# design.net
KiCad netlist of a schematic drawn in Altium Designer
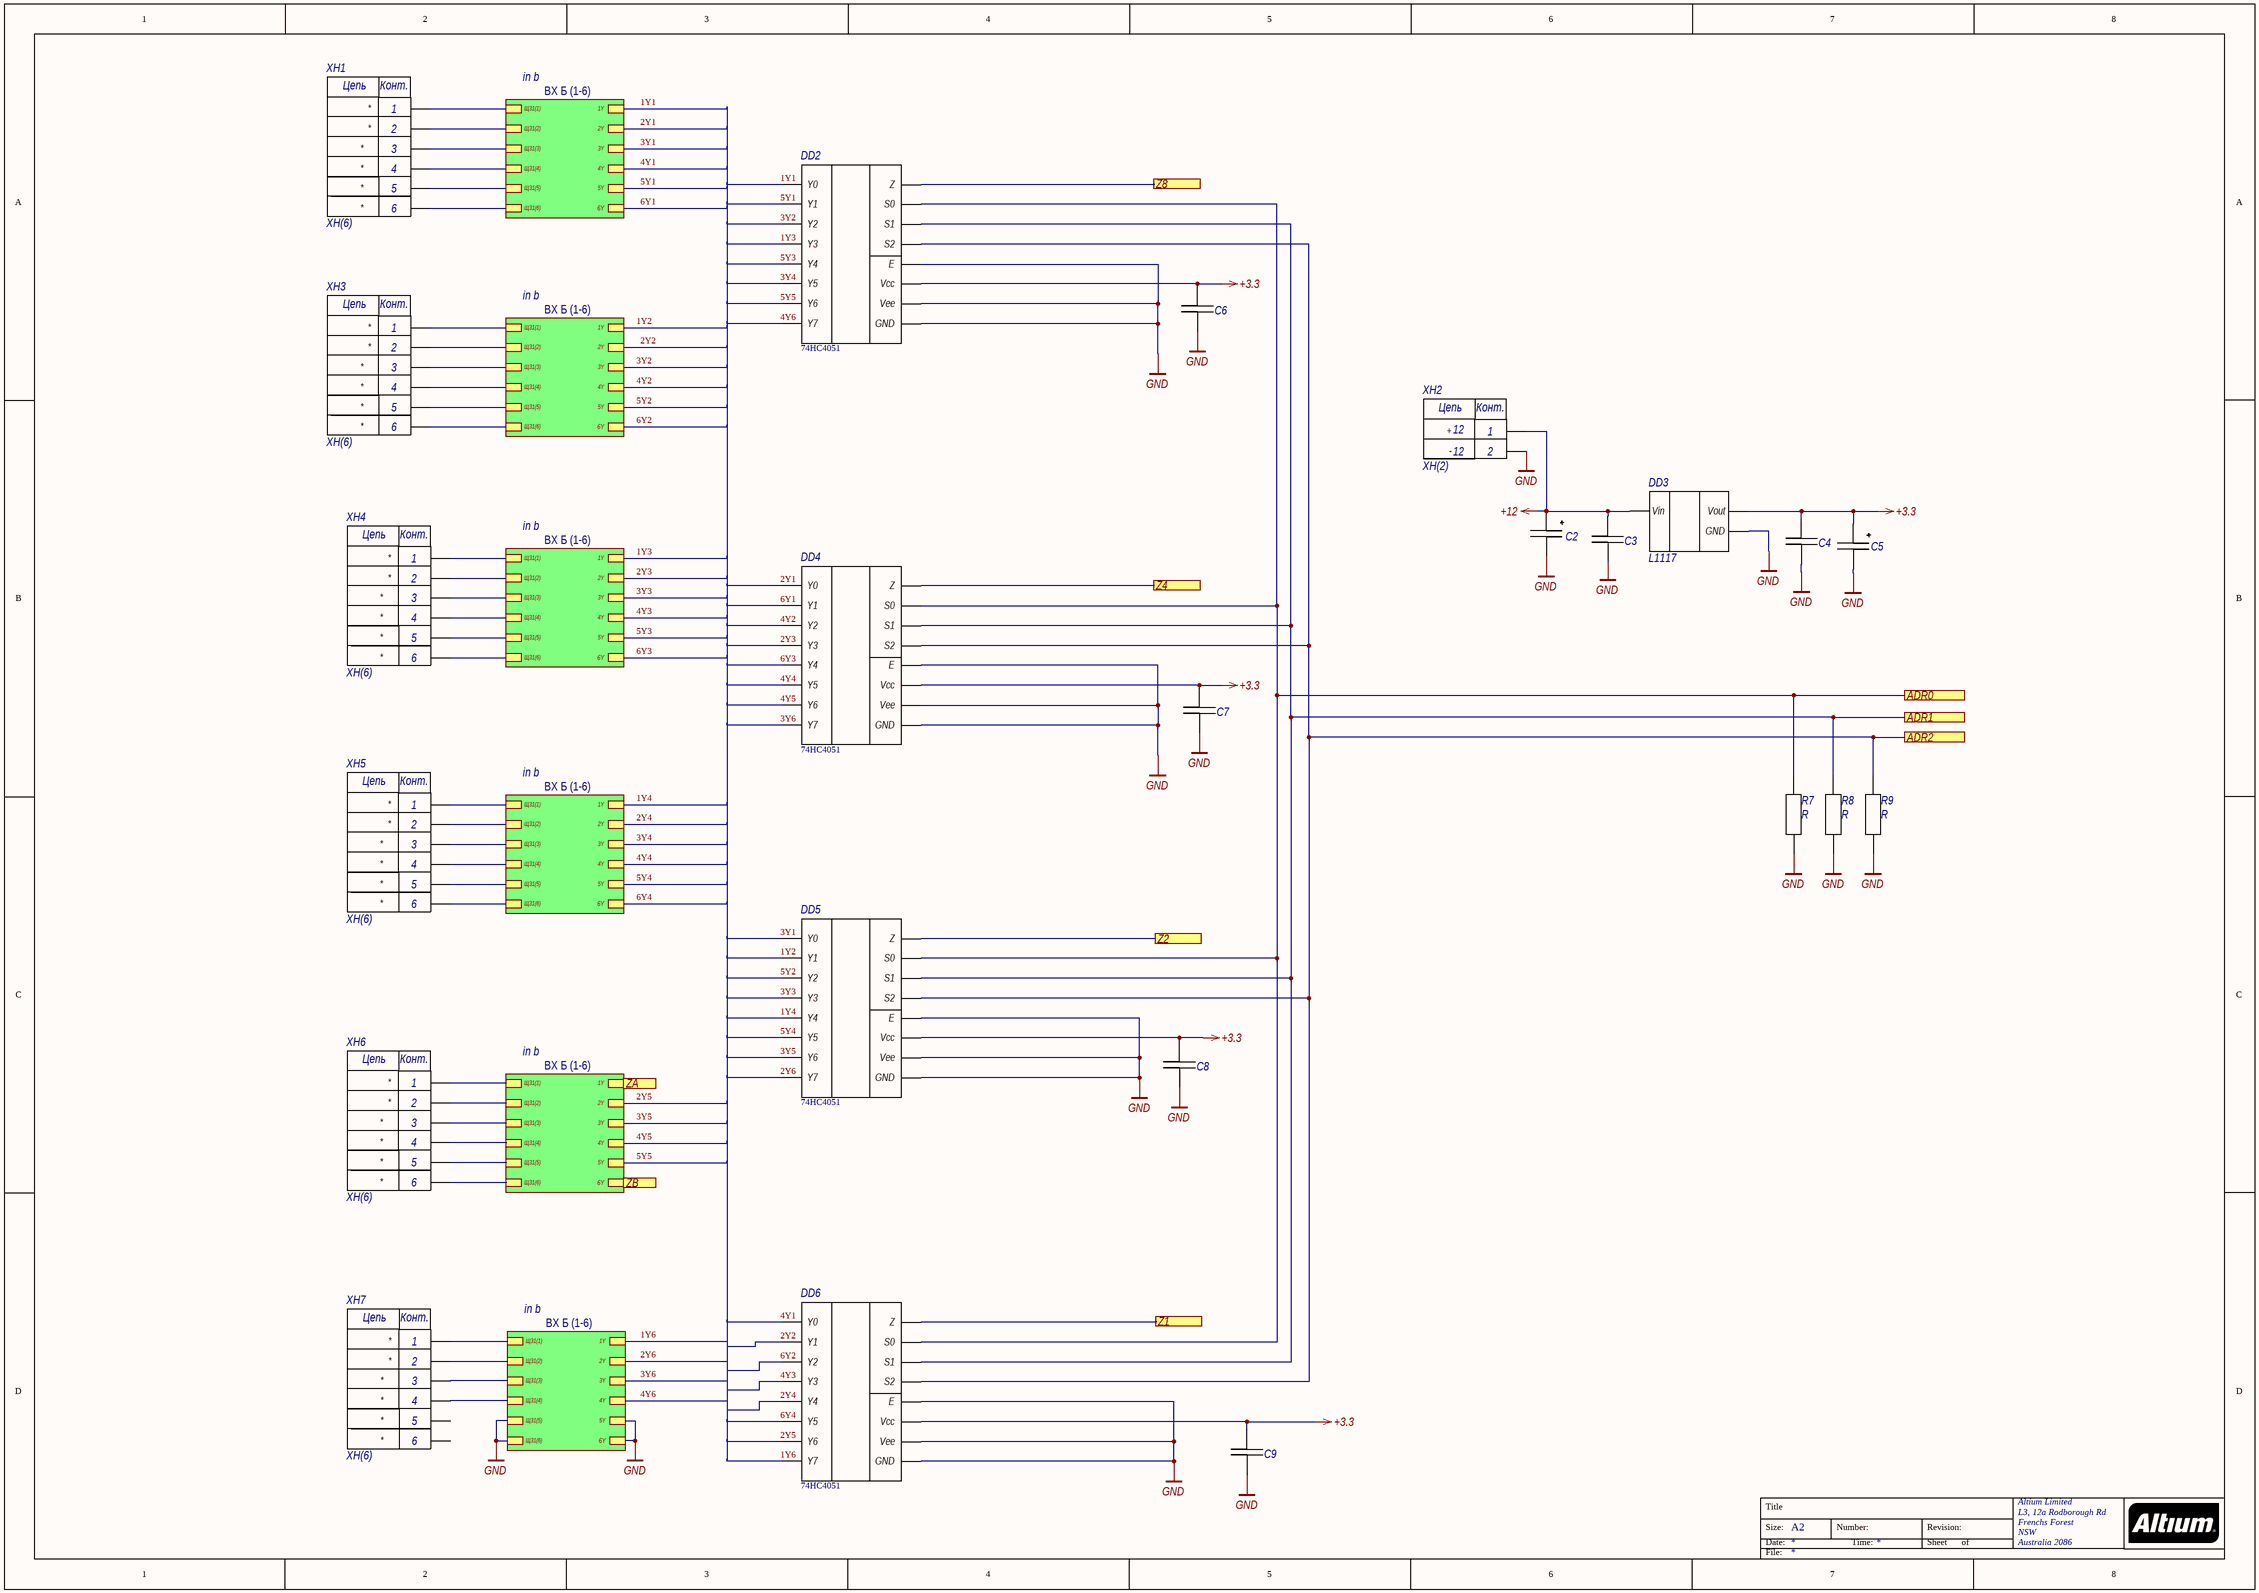
[diagram p0: СОГЛАСОВАНИЕ.SchDoc]

(export (version "E")
  (design (tool "Eeschema 10.0.6"))
  (components
    (comp (ref "C2") (value "C(AlEL)") (footprint "C(AlEL)") (libsource (lib "UGO") (part "C(AlEL)")))
    (comp (ref "C3")
      (value "C(ceramic)")
      (footprint "C(ceramic)")
      (libsource (lib "UGO") (part "C(ceramic)"))
    )
    (comp (ref "C4")
      (value "C(ceramic)")
      (footprint "C(ceramic)")
      (libsource (lib "UGO") (part "C(ceramic)"))
    )
    (comp (ref "C5") (value "C(AlEL)") (footprint "C(AlEL)") (libsource (lib "UGO") (part "C(AlEL)")))
    (comp (ref "C6")
      (value "C(ceramic)")
      (footprint "C(ceramic)")
      (libsource (lib "UGO") (part "C(ceramic)"))
    )
    (comp (ref "C7")
      (value "C(ceramic)")
      (footprint "C(ceramic)")
      (libsource (lib "UGO") (part "C(ceramic)"))
    )
    (comp (ref "C8")
      (value "C(ceramic)")
      (footprint "C(ceramic)")
      (libsource (lib "UGO") (part "C(ceramic)"))
    )
    (comp (ref "C9")
      (value "C(ceramic)")
      (footprint "C(ceramic)")
      (libsource (lib "UGO") (part "C(ceramic)"))
    )
    (comp (ref "DD2") (value "74HC4051") (footprint "74HC4050(51)") (libsource (lib "UGO") (part "74HC4051")))
    (comp (ref "DD3") (value "L1117") (footprint "LDL1117") (libsource (lib "UGO") (part "LDL1117")))
    (comp (ref "DD4") (value "74HC4051") (footprint "74HC4050(51)") (libsource (lib "UGO") (part "74HC4051")))
    (comp (ref "DD5") (value "74HC4051") (footprint "74HC4050(51)") (libsource (lib "UGO") (part "74HC4051")))
    (comp (ref "DD6") (value "74HC4051") (footprint "74HC4050(51)") (libsource (lib "UGO") (part "74HC4051")))
    (comp (ref "R7") (value "R") (footprint "R") (libsource (lib "UGO") (part "R")))
    (comp (ref "R8") (value "R") (footprint "R") (libsource (lib "UGO") (part "R")))
    (comp (ref "R9") (value "R") (footprint "R") (libsource (lib "UGO") (part "R")))
    (comp (ref "XH1") (value "ХH(6)") (footprint "XH(6)") (libsource (lib "UGO") (part "ХH(6)")))
    (comp (ref "XH2") (value "ХН(2)") (footprint "ХН(2)") (libsource (lib "UGO") (part "ХН(2)")))
    (comp (ref "XH3") (value "ХH(6)") (footprint "XH(6)") (libsource (lib "UGO") (part "ХH(6)")))
    (comp (ref "XH4") (value "ХH(6)") (footprint "XH(6)") (libsource (lib "UGO") (part "ХH(6)")))
    (comp (ref "XH5") (value "ХH(6)") (footprint "XH(6)") (libsource (lib "UGO") (part "ХH(6)")))
    (comp (ref "XH6") (value "ХH(6)") (footprint "XH(6)") (libsource (lib "UGO") (part "ХH(6)")))
    (comp (ref "XH7") (value "ХH(6)") (footprint "XH(6)") (libsource (lib "UGO") (part "ХH(6)")))
  )
  (nets
    (net (code "1") (name "+3.3") (class "Default")
      (node (ref "C4") (pin "2") (pintype "passive"))
      (node (ref "C5") (pin "1") (pintype "passive"))
      (node (ref "C6") (pin "2") (pintype "passive"))
      (node (ref "C7") (pin "2") (pintype "passive"))
      (node (ref "C8") (pin "2") (pintype "passive"))
      (node (ref "C9") (pin "2") (pintype "passive"))
      (node (ref "DD2") (pin "16") (pinfunction "Vcc_16") (pintype "passive"))
      (node (ref "DD3") (pin "2") (pinfunction "Vout_2") (pintype "passive"))
      (node (ref "DD4") (pin "16") (pinfunction "Vcc_16") (pintype "passive"))
      (node (ref "DD5") (pin "16") (pinfunction "Vcc_16") (pintype "passive"))
      (node (ref "DD6") (pin "16") (pinfunction "Vcc_16") (pintype "passive"))
    )
    (net (code "2") (name "+12") (class "Default")
      (node (ref "C2") (pin "1") (pintype "passive"))
      (node (ref "C3") (pin "2") (pintype "passive"))
      (node (ref "DD3") (pin "3") (pinfunction "Vin_3") (pintype "passive"))
      (node (ref "XH2") (pin "1") (pinfunction "+_1") (pintype "passive"))
    )
    (net (code "3") (name "/1Y1") (class "Default")
      (node (ref "DD2") (pin "13") (pinfunction "Y0_13") (pintype "passive"))
    )
    (net (code "4") (name "/1Y2") (class "Default")
      (node (ref "DD5") (pin "14") (pinfunction "Y1_14") (pintype "passive"))
    )
    (net (code "5") (name "/1Y3") (class "Default")
      (node (ref "DD2") (pin "12") (pinfunction "Y3_12") (pintype "passive"))
    )
    (net (code "6") (name "/1Y4") (class "Default")
      (node (ref "DD5") (pin "1") (pinfunction "Y4_1") (pintype "passive"))
    )
    (net (code "7") (name "/1Y6") (class "Default")
      (node (ref "DD6") (pin "4") (pinfunction "Y7_4") (pintype "passive"))
    )
    (net (code "8") (name "/2Y1") (class "Default")
      (node (ref "DD4") (pin "13") (pinfunction "Y0_13") (pintype "passive"))
    )
    (net (code "9") (name "/2Y2") (class "Default")
      (node (ref "DD6") (pin "14") (pinfunction "Y1_14") (pintype "passive"))
    )
    (net (code "10") (name "/2Y3") (class "Default")
      (node (ref "DD4") (pin "12") (pinfunction "Y3_12") (pintype "passive"))
    )
    (net (code "11") (name "/2Y4") (class "Default")
      (node (ref "DD6") (pin "1") (pinfunction "Y4_1") (pintype "passive"))
    )
    (net (code "12") (name "/2Y5") (class "Default")
      (node (ref "DD6") (pin "2") (pinfunction "Y6_2") (pintype "passive"))
    )
    (net (code "13") (name "/2Y6") (class "Default")
      (node (ref "DD5") (pin "4") (pinfunction "Y7_4") (pintype "passive"))
    )
    (net (code "14") (name "/3Y1") (class "Default")
      (node (ref "DD5") (pin "13") (pinfunction "Y0_13") (pintype "passive"))
    )
    (net (code "15") (name "/3Y2") (class "Default")
      (node (ref "DD2") (pin "15") (pinfunction "Y2_15") (pintype "passive"))
    )
    (net (code "16") (name "/3Y3") (class "Default")
      (node (ref "DD5") (pin "12") (pinfunction "Y3_12") (pintype "passive"))
    )
    (net (code "17") (name "/3Y4") (class "Default")
      (node (ref "DD2") (pin "5") (pinfunction "Y5_5") (pintype "passive"))
    )
    (net (code "18") (name "/3Y5") (class "Default")
      (node (ref "DD5") (pin "2") (pinfunction "Y6_2") (pintype "passive"))
    )
    (net (code "19") (name "/3Y6") (class "Default")
      (node (ref "DD4") (pin "4") (pinfunction "Y7_4") (pintype "passive"))
    )
    (net (code "20") (name "/4Y1") (class "Default")
      (node (ref "DD6") (pin "13") (pinfunction "Y0_13") (pintype "passive"))
    )
    (net (code "21") (name "/4Y2") (class "Default")
      (node (ref "DD4") (pin "15") (pinfunction "Y2_15") (pintype "passive"))
    )
    (net (code "22") (name "/4Y3") (class "Default")
      (node (ref "DD6") (pin "12") (pinfunction "Y3_12") (pintype "passive"))
    )
    (net (code "23") (name "/4Y4") (class "Default")
      (node (ref "DD4") (pin "5") (pinfunction "Y5_5") (pintype "passive"))
    )
    (net (code "24") (name "/4Y5") (class "Default")
      (node (ref "DD4") (pin "2") (pinfunction "Y6_2") (pintype "passive"))
    )
    (net (code "25") (name "/4Y6") (class "Default")
      (node (ref "DD2") (pin "4") (pinfunction "Y7_4") (pintype "passive"))
    )
    (net (code "26") (name "/5Y1") (class "Default")
      (node (ref "DD2") (pin "14") (pinfunction "Y1_14") (pintype "passive"))
    )
    (net (code "27") (name "/5Y2") (class "Default")
      (node (ref "DD5") (pin "15") (pinfunction "Y2_15") (pintype "passive"))
    )
    (net (code "28") (name "/5Y3") (class "Default")
      (node (ref "DD2") (pin "1") (pinfunction "Y4_1") (pintype "passive"))
    )
    (net (code "29") (name "/5Y4") (class "Default")
      (node (ref "DD5") (pin "5") (pinfunction "Y5_5") (pintype "passive"))
    )
    (net (code "30") (name "/5Y5") (class "Default")
      (node (ref "DD2") (pin "2") (pinfunction "Y6_2") (pintype "passive"))
    )
    (net (code "31") (name "/6Y1") (class "Default")
      (node (ref "DD4") (pin "14") (pinfunction "Y1_14") (pintype "passive"))
    )
    (net (code "32") (name "/6Y2") (class "Default")
      (node (ref "DD6") (pin "15") (pinfunction "Y2_15") (pintype "passive"))
    )
    (net (code "33") (name "/6Y3") (class "Default")
      (node (ref "DD4") (pin "1") (pinfunction "Y4_1") (pintype "passive"))
    )
    (net (code "34") (name "/6Y4") (class "Default")
      (node (ref "DD6") (pin "5") (pinfunction "Y5_5") (pintype "passive"))
    )
    (net (code "35") (name "/ADR0") (class "Default")
      (node (ref "DD2") (pin "11") (pinfunction "S0_11") (pintype "passive"))
      (node (ref "DD4") (pin "11") (pinfunction "S0_11") (pintype "passive"))
      (node (ref "DD5") (pin "11") (pinfunction "S0_11") (pintype "passive"))
      (node (ref "DD6") (pin "11") (pinfunction "S0_11") (pintype "passive"))
      (node (ref "R7") (pin "2") (pintype "passive"))
    )
    (net (code "36") (name "/ADR1") (class "Default")
      (node (ref "DD2") (pin "10") (pinfunction "S1_10") (pintype "passive"))
      (node (ref "DD4") (pin "10") (pinfunction "S1_10") (pintype "passive"))
      (node (ref "DD5") (pin "10") (pinfunction "S1_10") (pintype "passive"))
      (node (ref "DD6") (pin "10") (pinfunction "S1_10") (pintype "passive"))
      (node (ref "R8") (pin "2") (pintype "passive"))
    )
    (net (code "37") (name "/ADR2") (class "Default")
      (node (ref "DD2") (pin "9") (pinfunction "S2_9") (pintype "passive"))
      (node (ref "DD4") (pin "9") (pinfunction "S2_9") (pintype "passive"))
      (node (ref "DD5") (pin "9") (pinfunction "S2_9") (pintype "passive"))
      (node (ref "DD6") (pin "9") (pinfunction "S2_9") (pintype "passive"))
      (node (ref "R9") (pin "2") (pintype "passive"))
    )
    (net (code "38") (name "/Z1") (class "Default")
      (node (ref "DD6") (pin "3") (pinfunction "Z_3") (pintype "passive"))
    )
    (net (code "39") (name "/Z2") (class "Default")
      (node (ref "DD5") (pin "3") (pinfunction "Z_3") (pintype "passive"))
    )
    (net (code "40") (name "/Z4") (class "Default")
      (node (ref "DD4") (pin "3") (pinfunction "Z_3") (pintype "passive"))
    )
    (net (code "41") (name "/Z8") (class "Default")
      (node (ref "DD2") (pin "3") (pinfunction "Z_3") (pintype "passive"))
    )
    (net (code "44") (name "/Щ31(1)") (class "Default")
      (node (ref "XH7") (pin "1") (pinfunction "*_1") (pintype "passive"))
    )
    (net (code "45") (name "/Щ31(1)_1") (class "Default")
      (node (ref "XH3") (pin "1") (pinfunction "*_1") (pintype "passive"))
    )
    (net (code "46") (name "/Щ31(1)_2") (class "Default")
      (node (ref "XH1") (pin "1") (pinfunction "*_1") (pintype "passive"))
    )
    (net (code "47") (name "/Щ31(1)_3") (class "Default")
      (node (ref "XH4") (pin "1") (pinfunction "*_1") (pintype "passive"))
    )
    (net (code "48") (name "/Щ31(1)_4") (class "Default")
      (node (ref "XH5") (pin "1") (pinfunction "*_1") (pintype "passive"))
    )
    (net (code "49") (name "/Щ31(1)_5") (class "Default")
      (node (ref "XH6") (pin "1") (pinfunction "*_1") (pintype "passive"))
    )
    (net (code "50") (name "/Щ31(2)") (class "Default")
      (node (ref "XH7") (pin "2") (pinfunction "*_2") (pintype "passive"))
    )
    (net (code "51") (name "/Щ31(2)_1") (class "Default")
      (node (ref "XH3") (pin "2") (pinfunction "*_2") (pintype "passive"))
    )
    (net (code "52") (name "/Щ31(2)_2") (class "Default")
      (node (ref "XH1") (pin "2") (pinfunction "*_2") (pintype "passive"))
    )
    (net (code "53") (name "/Щ31(2)_3") (class "Default")
      (node (ref "XH4") (pin "2") (pinfunction "*_2") (pintype "passive"))
    )
    (net (code "54") (name "/Щ31(2)_4") (class "Default")
      (node (ref "XH5") (pin "2") (pinfunction "*_2") (pintype "passive"))
    )
    (net (code "55") (name "/Щ31(2)_5") (class "Default")
      (node (ref "XH6") (pin "2") (pinfunction "*_2") (pintype "passive"))
    )
    (net (code "56") (name "/Щ31(3)") (class "Default")
      (node (ref "XH7") (pin "3") (pinfunction "*_3") (pintype "passive"))
    )
    (net (code "57") (name "/Щ31(3)_1") (class "Default")
      (node (ref "XH3") (pin "3") (pinfunction "*_3") (pintype "passive"))
    )
    (net (code "58") (name "/Щ31(3)_2") (class "Default")
      (node (ref "XH1") (pin "3") (pinfunction "*_3") (pintype "passive"))
    )
    (net (code "59") (name "/Щ31(3)_3") (class "Default")
      (node (ref "XH4") (pin "3") (pinfunction "*_3") (pintype "passive"))
    )
    (net (code "60") (name "/Щ31(3)_4") (class "Default")
      (node (ref "XH5") (pin "3") (pinfunction "*_3") (pintype "passive"))
    )
    (net (code "61") (name "/Щ31(3)_5") (class "Default")
      (node (ref "XH6") (pin "3") (pinfunction "*_3") (pintype "passive"))
    )
    (net (code "62") (name "/Щ31(4)") (class "Default")
      (node (ref "XH7") (pin "4") (pinfunction "*_4") (pintype "passive"))
    )
    (net (code "63") (name "/Щ31(4)_1") (class "Default")
      (node (ref "XH3") (pin "4") (pinfunction "*_4") (pintype "passive"))
    )
    (net (code "64") (name "/Щ31(4)_2") (class "Default")
      (node (ref "XH1") (pin "4") (pinfunction "*_4") (pintype "passive"))
    )
    (net (code "65") (name "/Щ31(4)_3") (class "Default")
      (node (ref "XH4") (pin "4") (pinfunction "*_4") (pintype "passive"))
    )
    (net (code "66") (name "/Щ31(4)_4") (class "Default")
      (node (ref "XH5") (pin "4") (pinfunction "*_4") (pintype "passive"))
    )
    (net (code "67") (name "/Щ31(4)_5") (class "Default")
      (node (ref "XH6") (pin "4") (pinfunction "*_4") (pintype "passive"))
    )
    (net (code "68") (name "/Щ31(5)") (class "Default")
      (node (ref "XH6") (pin "5") (pinfunction "*_5") (pintype "passive"))
    )
    (net (code "69") (name "/Щ31(5)_1") (class "Default")
      (node (ref "XH3") (pin "5") (pinfunction "*_5") (pintype "passive"))
    )
    (net (code "70") (name "/Щ31(5)_2") (class "Default")
      (node (ref "XH1") (pin "5") (pinfunction "*_5") (pintype "passive"))
    )
    (net (code "71") (name "/Щ31(5)_3") (class "Default")
      (node (ref "XH4") (pin "5") (pinfunction "*_5") (pintype "passive"))
    )
    (net (code "72") (name "/Щ31(5)_4") (class "Default")
      (node (ref "XH5") (pin "5") (pinfunction "*_5") (pintype "passive"))
    )
    (net (code "73") (name "/Щ31(6)") (class "Default")
      (node (ref "XH6") (pin "6") (pinfunction "*_6") (pintype "passive"))
    )
    (net (code "74") (name "/Щ31(6)_1") (class "Default")
      (node (ref "XH3") (pin "6") (pinfunction "*_6") (pintype "passive"))
    )
    (net (code "75") (name "/Щ31(6)_2") (class "Default")
      (node (ref "XH1") (pin "6") (pinfunction "*_6") (pintype "passive"))
    )
    (net (code "76") (name "/Щ31(6)_3") (class "Default")
      (node (ref "XH4") (pin "6") (pinfunction "*_6") (pintype "passive"))
    )
    (net (code "77") (name "/Щ31(6)_4") (class "Default")
      (node (ref "XH5") (pin "6") (pinfunction "*_6") (pintype "passive"))
    )
    (net (code "78") (name "GND") (class "Default")
      (node (ref "C2") (pin "2") (pintype "passive"))
      (node (ref "C3") (pin "1") (pintype "passive"))
      (node (ref "C4") (pin "1") (pintype "passive"))
      (node (ref "C5") (pin "2") (pintype "passive"))
      (node (ref "C6") (pin "1") (pintype "passive"))
      (node (ref "C7") (pin "1") (pintype "passive"))
      (node (ref "C8") (pin "1") (pintype "passive"))
      (node (ref "C9") (pin "1") (pintype "passive"))
      (node (ref "DD2") (pin "6") (pinfunction "E_6") (pintype "passive"))
      (node (ref "DD2") (pin "7") (pinfunction "Vee_7") (pintype "passive"))
      (node (ref "DD2") (pin "8") (pinfunction "GND_8") (pintype "passive"))
      (node (ref "DD3") (pin "1") (pinfunction "GND_1") (pintype "passive"))
      (node (ref "DD4") (pin "6") (pinfunction "E_6") (pintype "passive"))
      (node (ref "DD4") (pin "7") (pinfunction "Vee_7") (pintype "passive"))
      (node (ref "DD4") (pin "8") (pinfunction "GND_8") (pintype "passive"))
      (node (ref "DD5") (pin "6") (pinfunction "E_6") (pintype "passive"))
      (node (ref "DD5") (pin "7") (pinfunction "Vee_7") (pintype "passive"))
      (node (ref "DD5") (pin "8") (pinfunction "GND_8") (pintype "passive"))
      (node (ref "DD6") (pin "6") (pinfunction "E_6") (pintype "passive"))
      (node (ref "DD6") (pin "7") (pinfunction "Vee_7") (pintype "passive"))
      (node (ref "DD6") (pin "8") (pinfunction "GND_8") (pintype "passive"))
      (node (ref "R7") (pin "1") (pintype "passive"))
      (node (ref "R8") (pin "1") (pintype "passive"))
      (node (ref "R9") (pin "1") (pintype "passive"))
      (node (ref "XH2") (pin "2") (pinfunction "-_2") (pintype "passive"))
    )
    (net (code "79") (name "unconnected-(XH7-*-Pad5)") (class "Default")
      (node (ref "XH7") (pin "5") (pinfunction "*_5") (pintype "passive"))
    )
    (net (code "80") (name "unconnected-(XH7-*-Pad6)") (class "Default")
      (node (ref "XH7") (pin "6") (pinfunction "*_6") (pintype "passive"))
    )
  )
)
